# mcu.net
KiCad netlist of a schematic drawn in Altium Designer
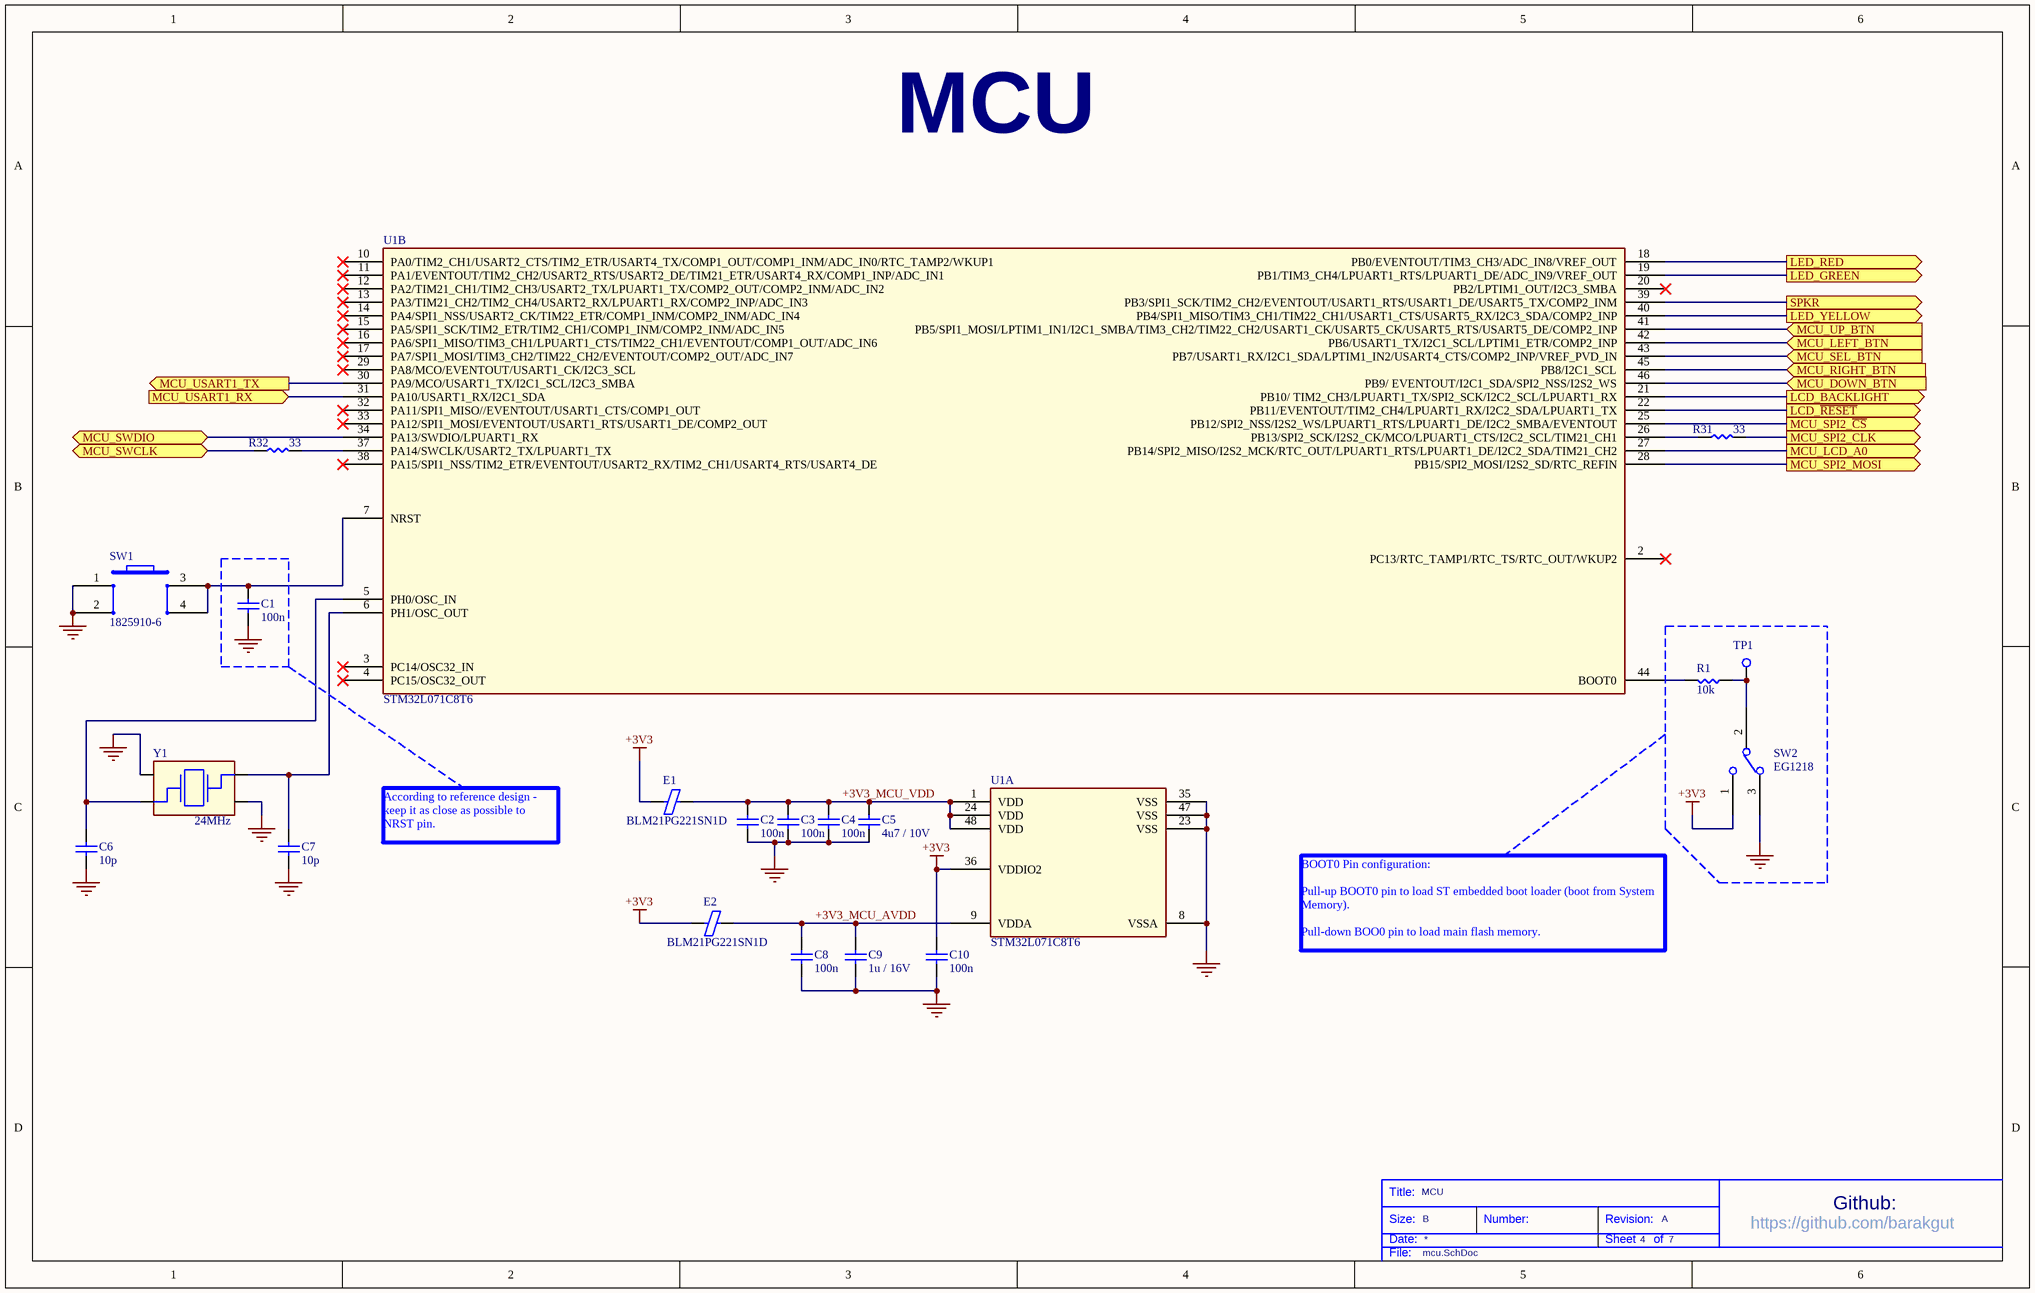
[diagram p0: mcu.SchDoc]

(export (version "E")
  (design (tool "Eeschema 10.0.6"))
  (components
    (comp (ref "C1")
      (value "100n")
      (footprint "C0402")
      (fields
        (field (name "MANUFACTURER") "TDK")
        (field (name "PCN PART NUMBER") "MLCC Part Number Change 30/Nov/2012")
        (field (name "TOLERANCE") "±10%")
      )
      (libsource (lib "rookieboard_symbols") (part "CGA2B3X7R1E104K050BB"))
    )
    (comp (ref "C2")
      (value "100n")
      (footprint "C0402")
      (fields
        (field (name "MANUFACTURER") "TDK")
        (field (name "PCN PART NUMBER") "MLCC Part Number Change 30/Nov/2012")
        (field (name "TOLERANCE") "±10%")
      )
      (libsource (lib "rookieboard_symbols") (part "CGA2B3X7R1E104K050BB"))
    )
    (comp (ref "C3")
      (value "100n")
      (footprint "C0402")
      (fields
        (field (name "MANUFACTURER") "TDK")
        (field (name "PCN PART NUMBER") "MLCC Part Number Change 30/Nov/2012")
        (field (name "TOLERANCE") "±10%")
      )
      (libsource (lib "rookieboard_symbols") (part "CGA2B3X7R1E104K050BB"))
    )
    (comp (ref "C4")
      (value "100n")
      (footprint "C0402")
      (fields
        (field (name "MANUFACTURER") "TDK")
        (field (name "PCN PART NUMBER") "MLCC Part Number Change 30/Nov/2012")
        (field (name "TOLERANCE") "±10%")
      )
      (libsource (lib "rookieboard_symbols") (part "CGA2B3X7R1E104K050BB"))
    )
    (comp (ref "C5")
      (value "4u7 / 10V")
      (footprint "C0805")
      (fields
        (field (name "MANUFACTURER") "TDK")
        (field (name "TOLERANCE") "±10%")
        (field (name "MANUFACTURER PART NUMBER") "C2012X7R1A475K085AC")
      )
      (libsource (lib "rookieboard_symbols") (part "C2012X7R1A475K085AC"))
    )
    (comp (ref "C6")
      (value "10p")
      (footprint "C0402")
      (description "Cap Ceramic 10pF 50V C0G 1% SMD 0402 125C Paper T/R")
      (fields (field (name "MANUFACTURER") "Yageo") (field (name "VOLTAGE") "50VDC"))
      (libsource (lib "rookieboard_symbols") (part "CC0402FRNPO9BN100"))
    )
    (comp (ref "C7")
      (value "10p")
      (footprint "C0402")
      (description "Cap Ceramic 10pF 50V C0G 1% SMD 0402 125C Paper T/R")
      (fields (field (name "MANUFACTURER") "Yageo") (field (name "VOLTAGE") "50VDC"))
      (libsource (lib "rookieboard_symbols") (part "CC0402FRNPO9BN100"))
    )
    (comp (ref "C8")
      (value "100n")
      (footprint "C0402")
      (fields
        (field (name "MANUFACTURER") "TDK")
        (field (name "PCN PART NUMBER") "MLCC Part Number Change 30/Nov/2012")
        (field (name "TOLERANCE") "±10%")
      )
      (libsource (lib "rookieboard_symbols") (part "CGA2B3X7R1E104K050BB"))
    )
    (comp (ref "C9")
      (value "1u / 16V")
      (footprint "C0805")
      (description "Multilayer Ceramic Capacitors MLCC - SMD/SMT 16volts 1uF X7R 10%")
      (fields (field (name "MANUFACTURER") "KEMET") (field (name "VOLTAGE") "16 Vdc"))
      (libsource (lib "rookieboard_symbols") (part "C0805C105K4RAC7800"))
    )
    (comp (ref "C10")
      (value "100n")
      (footprint "C0402")
      (fields
        (field (name "MANUFACTURER") "TDK")
        (field (name "PCN PART NUMBER") "MLCC Part Number Change 30/Nov/2012")
        (field (name "TOLERANCE") "±10%")
      )
      (libsource (lib "rookieboard_symbols") (part "CGA2B3X7R1E104K050BB"))
    )
    (comp (ref "E1")
      (value "BLM21PG221SN1D")
      (footprint "R0805")
      (description "FERRITE CHIP 220 OHM 0805")
      (fields (field (name "MANUFACTURER") "Murata"))
      (libsource (lib "rookieboard_symbols") (part "BLM21PG221SN1D"))
    )
    (comp (ref "E2")
      (value "BLM21PG221SN1D")
      (footprint "R0805")
      (description "FERRITE CHIP 220 OHM 0805")
      (fields (field (name "MANUFACTURER") "Murata"))
      (libsource (lib "rookieboard_symbols") (part "BLM21PG221SN1D"))
    )
    (comp (ref "R1")
      (value "10k")
      (footprint "R0805")
      (description "RES SMD 10K OHM 1% 1/8W 0805")
      (fields (field (name "MANUFACTURER") "Yageo") (field (name "TOLERANCE") "1 %"))
      (libsource (lib "rookieboard_symbols") (part "RC0805FR-0710KL"))
    )
    (comp (ref "R31")
      (value "33")
      (footprint "R0402")
      (fields
        (field (name "MANUFACTURER") "Yageo")
        (field (name "MANUFACTURER PART NUMBER") "RC0402FR-0733RL")
      )
      (libsource (lib "rookieboard_symbols") (part "RC0402FR-0733RL"))
    )
    (comp (ref "R32")
      (value "33")
      (footprint "R0402")
      (fields
        (field (name "MANUFACTURER") "Yageo")
        (field (name "MANUFACTURER PART NUMBER") "RC0402FR-0733RL")
      )
      (libsource (lib "rookieboard_symbols") (part "RC0402FR-0733RL"))
    )
    (comp (ref "SW1")
      (value "1825910-6")
      (footprint "1825910-6")
      (description "Switch Push Button OFF (ON) SPST Round Button 0.05A 24VDC Momentary Contact PC Pins Thru-Hole")
      (fields (field (name "MANUFACTURER") "TE Connectivity Alcoswitch"))
      (libsource (lib "rookieboard_symbols") (part "1825910-6"))
    )
    (comp (ref "SW2")
      (value "EG1218")
      (footprint "EG1218")
      (description "E-SWITCH         EG1218             SLIDE SWITCH, SPDT, 200MA")
      (fields (field (name "MANUFACTURER") "E-Switch"))
      (libsource (lib "rookieboard_symbols") (part "EG1218"))
    )
    (comp (ref "TP1")
      (value "Test Pad 1mm")
      (footprint "TP_1MM")
      (libsource (lib "rookieboard_symbols") (part "TEST_PAD_1mm"))
    )
    (comp (ref "U1")
      (value "STM32L071C8T6")
      (footprint "LQFP48")
      (description "ARM® Cortex®-M0+ STM32L0 Microcontroller IC 32-Bit 32MHz 64KB (64K x 8) FLASH 48-LQFP (7x7)")
      (fields (field (name "MANUFACTURER") "STMicroelectronics"))
      (libsource (lib "rookieboard_symbols") (part "STM32L071C8T6"))
    )
    (comp (ref "Y1")
      (value "24MHz")
      (footprint "ABM10AIG-24.000MHZ-4Z-T3")
      (fields
        (field (name "MANUFACTURER") "Abracon")
        (field (name "MANUFACTURER PART NUMBER") "ABM10AIG24.000MHZ4ZT3")
      )
      (libsource (lib "rookieboard_symbols") (part "ABM10AIG24.000MHZ4ZT3"))
    )
  )
  (nets
    (net (code "1") (name "+3V3") (class "Default")
      (node (ref "C10") (pin "2") (pinfunction "2_2") (pintype "passive"))
      (node (ref "E1") (pin "1") (pinfunction "1_1") (pintype "passive"))
      (node (ref "E2") (pin "1") (pinfunction "1_1") (pintype "passive"))
      (node (ref "SW2") (pin "1") (pinfunction "1_1") (pintype "passive"))
      (node (ref "U1") (pin "36") (pinfunction "VDDIO2_36") (pintype "power_in"))
    )
    (net (code "2") (name "/+3V3_MCU_AVDD") (class "Default")
      (node (ref "C8") (pin "2") (pinfunction "2_2") (pintype "passive"))
      (node (ref "C9") (pin "2") (pinfunction "2_2") (pintype "passive"))
      (node (ref "E2") (pin "2") (pinfunction "2_2") (pintype "passive"))
      (node (ref "U1") (pin "9") (pinfunction "VDDA_9") (pintype "power_in"))
    )
    (net (code "3") (name "/+3V3_MCU_VDD") (class "Default")
      (node (ref "C2") (pin "2") (pinfunction "2_2") (pintype "passive"))
      (node (ref "C3") (pin "2") (pinfunction "2_2") (pintype "passive"))
      (node (ref "C4") (pin "2") (pinfunction "2_2") (pintype "passive"))
      (node (ref "C5") (pin "2") (pinfunction "2_2") (pintype "passive"))
      (node (ref "E1") (pin "2") (pinfunction "2_2") (pintype "passive"))
      (node (ref "U1") (pin "1") (pinfunction "VDD_1") (pintype "power_in"))
      (node (ref "U1") (pin "24") (pinfunction "VDD_24") (pintype "power_in"))
      (node (ref "U1") (pin "48") (pinfunction "VDD_48") (pintype "power_in"))
    )
    (net (code "4") (name "/LCD_BACKLIGHT") (class "Default")
      (node (ref "U1") (pin "21") (pinfunction "PB10/_TIM2_CH3/LPUART1_TX/SPI2_SCK/I2C2_SCL/LPUART1_RX_21") (pintype "passive"))
    )
    (net (code "5") (name "/LCD_~{RESET}") (class "Default")
      (node (ref "U1") (pin "22") (pinfunction "PB11/EVENTOUT/TIM2_CH4/LPUART1_RX/I2C2_SDA/LPUART1_TX_22") (pintype "passive"))
    )
    (net (code "6") (name "/LED_GREEN") (class "Default")
      (node (ref "U1") (pin "19") (pinfunction "PB1/TIM3_CH4/LPUART1_RTS/LPUART1_DE/ADC_IN9/VREF_OUT_19") (pintype "passive"))
    )
    (net (code "7") (name "/LED_RED") (class "Default")
      (node (ref "U1") (pin "18") (pinfunction "PB0/EVENTOUT/TIM3_CH3/ADC_IN8/VREF_OUT_18") (pintype "passive"))
    )
    (net (code "8") (name "/LED_YELLOW") (class "Default")
      (node (ref "U1") (pin "40") (pinfunction "PB4/SPI1_MISO/TIM3_CH1/TIM22_CH1/USART1_CTS/USART5_RX/I2C3_SDA/COMP2_INP_40") (pintype "passive"))
    )
    (net (code "9") (name "/MCU_DOWN_BTN") (class "Default")
      (node (ref "U1") (pin "46") (pinfunction "PB9/_EVENTOUT/I2C1_SDA/SPI2_NSS/I2S2_WS_46") (pintype "passive"))
    )
    (net (code "10") (name "/MCU_LCD_A0") (class "Default")
      (node (ref "U1") (pin "27") (pinfunction "PB14/SPI2_MISO/I2S2_MCK/RTC_OUT/LPUART1_RTS/LPUART1_DE/I2C2_SDA/TIM21_CH2_27") (pintype "passive"))
    )
    (net (code "11") (name "/MCU_LEFT_BTN") (class "Default")
      (node (ref "U1") (pin "42") (pinfunction "PB6/USART1_TX/I2C1_SCL/LPTIM1_ETR/COMP2_INP_42") (pintype "passive"))
    )
    (net (code "12") (name "/MCU_RIGHT_BTN") (class "Default")
      (node (ref "U1") (pin "45") (pinfunction "PB8/I2C1_SCL_45") (pintype "passive"))
    )
    (net (code "13") (name "/MCU_SEL_BTN") (class "Default")
      (node (ref "U1") (pin "43") (pinfunction "PB7/USART1_RX/I2C1_SDA/LPTIM1_IN2/USART4_CTS/COMP2_INP/VREF_PVD_IN_43") (pintype "passive"))
    )
    (net (code "14") (name "/MCU_SPI2_CLK") (class "Default")
      (node (ref "R31") (pin "2") (pinfunction "2_2") (pintype "passive"))
    )
    (net (code "15") (name "/MCU_SPI2_MOSI") (class "Default")
      (node (ref "U1") (pin "28") (pinfunction "PB15/SPI2_MOSI/I2S2_SD/RTC_REFIN_28") (pintype "passive"))
    )
    (net (code "16") (name "/MCU_SPI2_~{CS}") (class "Default")
      (node (ref "U1") (pin "25") (pinfunction "PB12/SPI2_NSS/I2S2_WS/LPUART1_RTS/LPUART1_DE/I2C2_SMBA/EVENTOUT_25") (pintype "passive"))
    )
    (net (code "17") (name "/MCU_SWCLK") (class "Default")
      (node (ref "R32") (pin "1") (pinfunction "1_1") (pintype "passive"))
    )
    (net (code "18") (name "/MCU_SWDIO") (class "Default")
      (node (ref "U1") (pin "34") (pinfunction "PA13/SWDIO/LPUART1_RX_34") (pintype "passive"))
    )
    (net (code "19") (name "/MCU_UP_BTN") (class "Default")
      (node (ref "U1") (pin "41") (pinfunction "PB5/SPI1_MOSI/LPTIM1_IN1/I2C1_SMBA/TIM3_CH2/TIM22_CH2/USART1_CK/USART5_CK/USART5_RTS/USART5_DE/COMP2_INP_41") (pintype "passive"))
    )
    (net (code "20") (name "/MCU_USART1_RX") (class "Default")
      (node (ref "U1") (pin "31") (pinfunction "PA10/USART1_RX/I2C1_SDA_31") (pintype "passive"))
    )
    (net (code "21") (name "/MCU_USART1_TX") (class "Default")
      (node (ref "U1") (pin "30") (pinfunction "PA9/MCO/USART1_TX/I2C1_SCL/I2C3_SMBA_30") (pintype "passive"))
    )
    (net (code "22") (name "/SPKR") (class "Default")
      (node (ref "U1") (pin "39") (pinfunction "PB3/SPI1_SCK/TIM2_CH2/EVENTOUT/USART1_RTS/USART1_DE/USART5_TX/COMP2_INM_39") (pintype "passive"))
    )
    (net (code "23") (name "GND") (class "Default")
      (node (ref "C1") (pin "1") (pinfunction "1_1") (pintype "passive"))
      (node (ref "C10") (pin "1") (pinfunction "1_1") (pintype "passive"))
      (node (ref "C2") (pin "1") (pinfunction "1_1") (pintype "passive"))
      (node (ref "C3") (pin "1") (pinfunction "1_1") (pintype "passive"))
      (node (ref "C4") (pin "1") (pinfunction "1_1") (pintype "passive"))
      (node (ref "C5") (pin "1") (pinfunction "1_1") (pintype "passive"))
      (node (ref "C6") (pin "1") (pinfunction "1_1") (pintype "passive"))
      (node (ref "C7") (pin "1") (pinfunction "1_1") (pintype "passive"))
      (node (ref "C8") (pin "1") (pinfunction "1_1") (pintype "passive"))
      (node (ref "C9") (pin "1") (pinfunction "1_1") (pintype "passive"))
      (node (ref "SW1") (pin "1") (pinfunction "1_1") (pintype "passive"))
      (node (ref "SW1") (pin "2") (pinfunction "2_2") (pintype "passive"))
      (node (ref "SW2") (pin "3") (pinfunction "3_3") (pintype "passive"))
      (node (ref "U1") (pin "23") (pinfunction "VSS_23") (pintype "power_in"))
      (node (ref "U1") (pin "35") (pinfunction "VSS_35") (pintype "power_in"))
      (node (ref "U1") (pin "47") (pinfunction "VSS_47") (pintype "power_in"))
      (node (ref "U1") (pin "8") (pinfunction "VSSA_8") (pintype "power_in"))
      (node (ref "Y1") (pin "2") (pinfunction "2_2") (pintype "passive"))
      (node (ref "Y1") (pin "4") (pinfunction "4_4") (pintype "passive"))
    )
    (net (code "24") (name "Net-(R1-Pad1)") (class "Default")
      (node (ref "R1") (pin "1") (pinfunction "1_1") (pintype "passive"))
      (node (ref "SW2") (pin "2") (pinfunction "2_2") (pintype "passive"))
      (node (ref "TP1") (pin "1") (pinfunction "1_1") (pintype "passive"))
    )
    (net (code "25") (name "Net-(U1B-BOOT0)") (class "Default")
      (node (ref "R1") (pin "2") (pinfunction "2_2") (pintype "passive"))
      (node (ref "U1") (pin "44") (pinfunction "BOOT0_44") (pintype "passive"))
    )
    (net (code "26") (name "Net-(U1B-NRST)") (class "Default")
      (node (ref "C1") (pin "2") (pinfunction "2_2") (pintype "passive"))
      (node (ref "SW1") (pin "3") (pinfunction "3_3") (pintype "passive"))
      (node (ref "SW1") (pin "4") (pinfunction "4_4") (pintype "passive"))
      (node (ref "U1") (pin "7") (pinfunction "NRST_7") (pintype "passive"))
    )
    (net (code "27") (name "Net-(U1B-PA14{slash}SWCLK{slash}USART2_TX{slash}LPUART1_TX)") (class "Default")
      (node (ref "R32") (pin "2") (pinfunction "2_2") (pintype "passive"))
      (node (ref "U1") (pin "37") (pinfunction "PA14/SWCLK/USART2_TX/LPUART1_TX_37") (pintype "passive"))
    )
    (net (code "28") (name "Net-(U1B-PB13{slash}SPI2_SCK{slash}I2S2_CK{slash}MCO{slash}LPUART1_CTS{slash}I2C2_SCL{slash}TIM21_CH1)") (class "Default")
      (node (ref "R31") (pin "1") (pinfunction "1_1") (pintype "passive"))
      (node (ref "U1") (pin "26") (pinfunction "PB13/SPI2_SCK/I2S2_CK/MCO/LPUART1_CTS/I2C2_SCL/TIM21_CH1_26") (pintype "passive"))
    )
    (net (code "29") (name "Net-(U1B-PH0{slash}OSC_IN)") (class "Default")
      (node (ref "C6") (pin "2") (pinfunction "2_2") (pintype "passive"))
      (node (ref "U1") (pin "5") (pinfunction "PH0/OSC_IN_5") (pintype "passive"))
      (node (ref "Y1") (pin "1") (pinfunction "1_1") (pintype "passive"))
    )
    (net (code "30") (name "Net-(U1B-PH1{slash}OSC_OUT)") (class "Default")
      (node (ref "C7") (pin "2") (pinfunction "2_2") (pintype "passive"))
      (node (ref "U1") (pin "6") (pinfunction "PH1/OSC_OUT_6") (pintype "passive"))
      (node (ref "Y1") (pin "3") (pinfunction "3_3") (pintype "passive"))
    )
    (net (code "31") (name "unconnected-(U1B-PA0{slash}TIM2_CH1{slash}USART2_CTS{slash}TIM2_ETR{slash}USART4_TX{slash}COMP1_OUT{slash}COMP1_INM{slash}ADC_IN0{slash}RTC_TAMP2{slash}WKUP1-Pad10)") (class "Default")
      (node (ref "U1") (pin "10") (pinfunction "PA0/TIM2_CH1/USART2_CTS/TIM2_ETR/USART4_TX/COMP1_OUT/COMP1_INM/ADC_IN0/RTC_TAMP2/WKUP1_10") (pintype "passive+no_connect"))
    )
    (net (code "32") (name "unconnected-(U1B-PA1{slash}EVENTOUT{slash}TIM2_CH2{slash}USART2_RTS{slash}USART2_DE{slash}TIM21_ETR{slash}USART4_RX{slash}COMP1_INP{slash}ADC_IN1-Pad11)") (class "Default")
      (node (ref "U1") (pin "11") (pinfunction "PA1/EVENTOUT/TIM2_CH2/USART2_RTS/USART2_DE/TIM21_ETR/USART4_RX/COMP1_INP/ADC_IN1_11") (pintype "passive+no_connect"))
    )
    (net (code "33") (name "unconnected-(U1B-PA2{slash}TIM21_CH1{slash}TIM2_CH3{slash}USART2_TX{slash}LPUART1_TX{slash}COMP2_OUT{slash}COMP2_INM{slash}ADC_IN2-Pad12)") (class "Default")
      (node (ref "U1") (pin "12") (pinfunction "PA2/TIM21_CH1/TIM2_CH3/USART2_TX/LPUART1_TX/COMP2_OUT/COMP2_INM/ADC_IN2_12") (pintype "passive+no_connect"))
    )
    (net (code "34") (name "unconnected-(U1B-PA3{slash}TIM21_CH2{slash}TIM2_CH4{slash}USART2_RX{slash}LPUART1_RX{slash}COMP2_INP{slash}ADC_IN3-Pad13)") (class "Default")
      (node (ref "U1") (pin "13") (pinfunction "PA3/TIM21_CH2/TIM2_CH4/USART2_RX/LPUART1_RX/COMP2_INP/ADC_IN3_13") (pintype "passive+no_connect"))
    )
    (net (code "35") (name "unconnected-(U1B-PA4{slash}SPI1_NSS{slash}USART2_CK{slash}TIM22_ETR{slash}COMP1_INM{slash}COMP2_INM{slash}ADC_IN4-Pad14)") (class "Default")
      (node (ref "U1") (pin "14") (pinfunction "PA4/SPI1_NSS/USART2_CK/TIM22_ETR/COMP1_INM/COMP2_INM/ADC_IN4_14") (pintype "passive+no_connect"))
    )
    (net (code "36") (name "unconnected-(U1B-PA5{slash}SPI1_SCK{slash}TIM2_ETR{slash}TIM2_CH1{slash}COMP1_INM{slash}COMP2_INM{slash}ADC_IN5-Pad15)") (class "Default")
      (node (ref "U1") (pin "15") (pinfunction "PA5/SPI1_SCK/TIM2_ETR/TIM2_CH1/COMP1_INM/COMP2_INM/ADC_IN5_15") (pintype "passive+no_connect"))
    )
    (net (code "37") (name "unconnected-(U1B-PA6{slash}SPI1_MISO{slash}TIM3_CH1{slash}LPUART1_CTS{slash}TIM22_CH1{slash}EVENTOUT{slash}COMP1_OUT{slash}ADC_IN6-Pad16)") (class "Default")
      (node (ref "U1") (pin "16") (pinfunction "PA6/SPI1_MISO/TIM3_CH1/LPUART1_CTS/TIM22_CH1/EVENTOUT/COMP1_OUT/ADC_IN6_16") (pintype "passive+no_connect"))
    )
    (net (code "38") (name "unconnected-(U1B-PA7{slash}SPI1_MOSI{slash}TIM3_CH2{slash}TIM22_CH2{slash}EVENTOUT{slash}COMP2_OUT{slash}ADC_IN7-Pad17)") (class "Default")
      (node (ref "U1") (pin "17") (pinfunction "PA7/SPI1_MOSI/TIM3_CH2/TIM22_CH2/EVENTOUT/COMP2_OUT/ADC_IN7_17") (pintype "passive+no_connect"))
    )
    (net (code "39") (name "unconnected-(U1B-PA8{slash}MCO{slash}EVENTOUT{slash}USART1_CK{slash}I2C3_SCL-Pad29)") (class "Default")
      (node (ref "U1") (pin "29") (pinfunction "PA8/MCO/EVENTOUT/USART1_CK/I2C3_SCL_29") (pintype "passive+no_connect"))
    )
    (net (code "40") (name "unconnected-(U1B-PA11{slash}SPI1_MISO{slash}{slash}EVENTOUT{slash}USART1_CTS{slash}COMP1_OUT-Pad32)") (class "Default")
      (node (ref "U1") (pin "32") (pinfunction "PA11/SPI1_MISO//EVENTOUT/USART1_CTS/COMP1_OUT_32") (pintype "passive+no_connect"))
    )
    (net (code "41") (name "unconnected-(U1B-PA12{slash}SPI1_MOSI{slash}EVENTOUT{slash}USART1_RTS{slash}USART1_DE{slash}COMP2_OUT-Pad33)") (class "Default")
      (node (ref "U1") (pin "33") (pinfunction "PA12/SPI1_MOSI/EVENTOUT/USART1_RTS/USART1_DE/COMP2_OUT_33") (pintype "passive+no_connect"))
    )
    (net (code "42") (name "unconnected-(U1B-PA15{slash}SPI1_NSS{slash}TIM2_ETR{slash}EVENTOUT{slash}USART2_RX{slash}TIM2_CH1{slash}USART4_RTS{slash}USART4_DE-Pad38)") (class "Default")
      (node (ref "U1") (pin "38") (pinfunction "PA15/SPI1_NSS/TIM2_ETR/EVENTOUT/USART2_RX/TIM2_CH1/USART4_RTS/USART4_DE_38") (pintype "passive+no_connect"))
    )
    (net (code "43") (name "unconnected-(U1B-PB2{slash}LPTIM1_OUT{slash}I2C3_SMBA-Pad20)") (class "Default")
      (node (ref "U1") (pin "20") (pinfunction "PB2/LPTIM1_OUT/I2C3_SMBA_20") (pintype "passive+no_connect"))
    )
    (net (code "44") (name "unconnected-(U1B-PC13{slash}RTC_TAMP1{slash}RTC_TS{slash}RTC_OUT{slash}WKUP2-Pad2)") (class "Default")
      (node (ref "U1") (pin "2") (pinfunction "PC13/RTC_TAMP1/RTC_TS/RTC_OUT/WKUP2_2") (pintype "passive+no_connect"))
    )
    (net (code "45") (name "unconnected-(U1B-PC14{slash}OSC32_IN-Pad3)") (class "Default")
      (node (ref "U1") (pin "3") (pinfunction "PC14/OSC32_IN_3") (pintype "passive+no_connect"))
    )
    (net (code "46") (name "unconnected-(U1B-PC15{slash}OSC32_OUT-Pad4)") (class "Default")
      (node (ref "U1") (pin "4") (pinfunction "PC15/OSC32_OUT_4") (pintype "passive+no_connect"))
    )
  )
)
